# Tray2_Power.net
KiCad netlist of a schematic drawn in Altium Designer
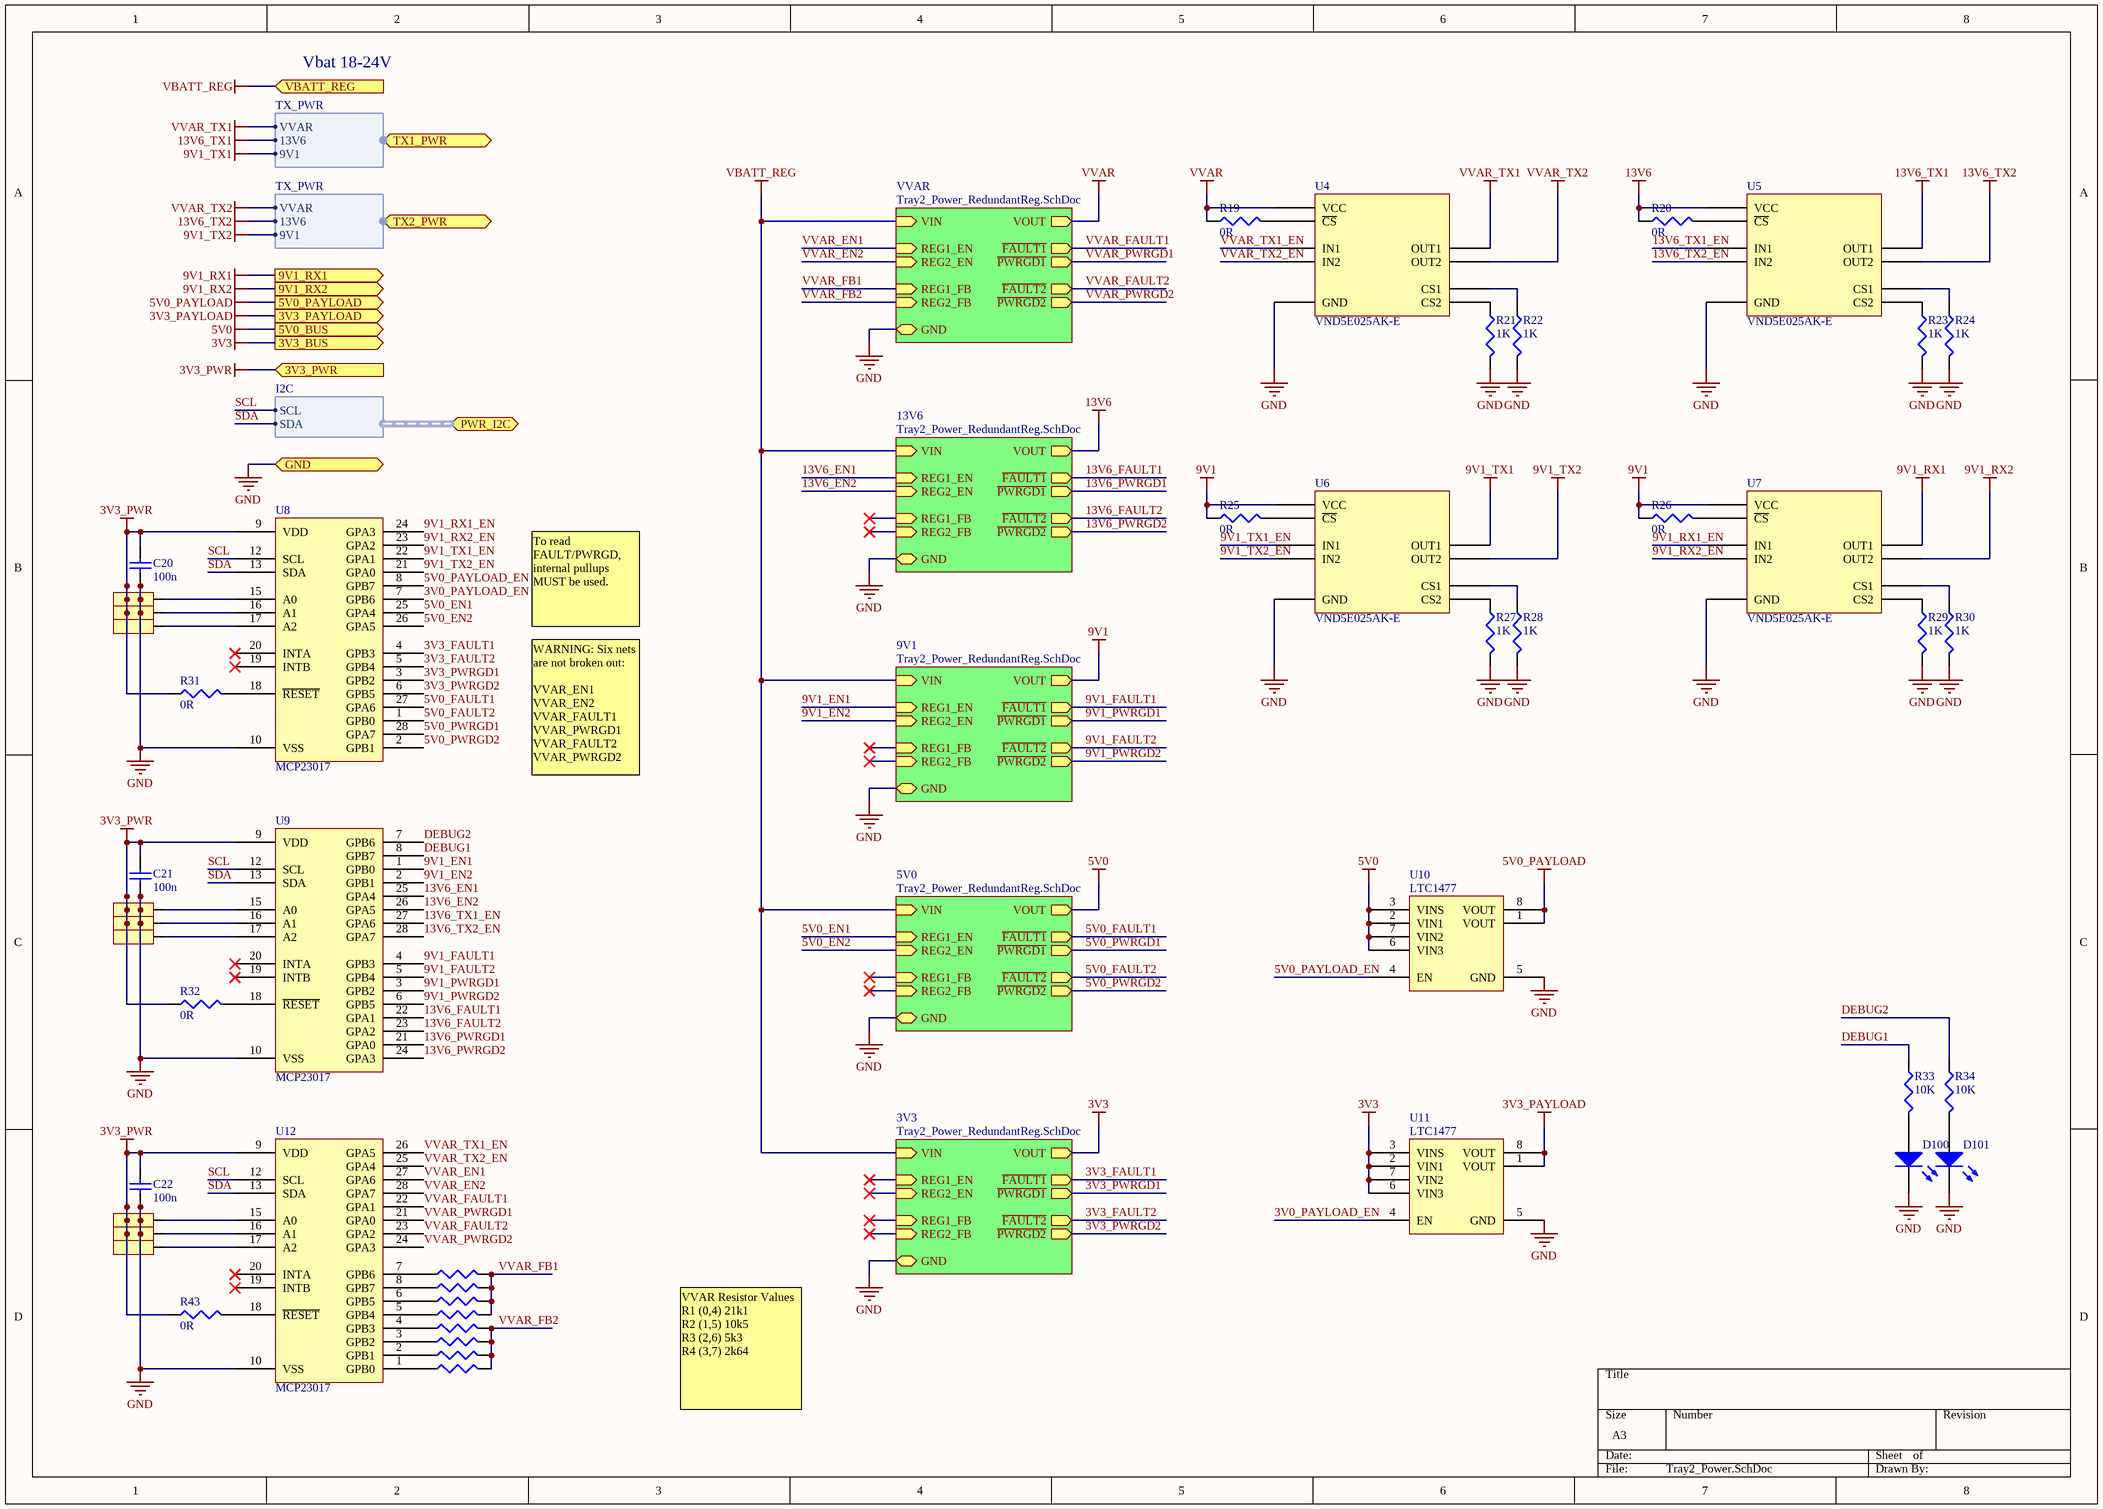
[diagram p0: Tray2_Power.SchDoc]

(export (version "E")
  (design (tool "Eeschema 10.0.6"))
  (components
    (comp (ref "C20")
      (value "100n")
      (footprint "R0805M")
      (description "Capacitor")
      (fields (field (name "PUBLISHER") "Altium Limited"))
      (libsource (lib "Miscellaneous Devices") (part "Cap"))
    )
    (comp (ref "C21")
      (value "100n")
      (footprint "R0805M")
      (description "Capacitor")
      (fields (field (name "PUBLISHER") "Altium Limited"))
      (libsource (lib "Miscellaneous Devices") (part "Cap"))
    )
    (comp (ref "C22")
      (value "100n")
      (footprint "R0805M")
      (description "Capacitor")
      (fields (field (name "PUBLISHER") "Altium Limited"))
      (libsource (lib "Miscellaneous Devices") (part "Cap"))
    )
    (comp (ref "D100")
      (value "LED0")
      (footprint "R0805M")
      (description "Typical INFRARED GaAs LED")
      (fields (field (name "PUBLISHER") "Altium Limited"))
      (libsource (lib "Miscellaneous Devices") (part "LED0"))
    )
    (comp (ref "D101")
      (value "LED0")
      (footprint "R0805M")
      (description "Typical INFRARED GaAs LED")
      (fields (field (name "PUBLISHER") "Altium Limited"))
      (libsource (lib "Miscellaneous Devices") (part "LED0"))
    )
    (comp (ref "J1")
      (value "3-WAY JUMPER")
      (footprint "J1205M")
      (libsource (lib "SchLib") (part "3-WAY JUMPER"))
    )
    (comp (ref "J2")
      (value "3-WAY JUMPER")
      (footprint "J1205M")
      (libsource (lib "SchLib") (part "3-WAY JUMPER"))
    )
    (comp (ref "J3")
      (value "3-WAY JUMPER")
      (footprint "J1205M")
      (libsource (lib "SchLib") (part "3-WAY JUMPER"))
    )
    (comp (ref "J4")
      (value "3-WAY JUMPER")
      (footprint "J1205M")
      (libsource (lib "SchLib") (part "3-WAY JUMPER"))
    )
    (comp (ref "J5")
      (value "3-WAY JUMPER")
      (footprint "J1205M")
      (libsource (lib "SchLib") (part "3-WAY JUMPER"))
    )
    (comp (ref "J6")
      (value "3-WAY JUMPER")
      (footprint "J1205M")
      (libsource (lib "SchLib") (part "3-WAY JUMPER"))
    )
    (comp (ref "J7")
      (value "3-WAY JUMPER")
      (footprint "J1205M")
      (libsource (lib "SchLib") (part "3-WAY JUMPER"))
    )
    (comp (ref "J8")
      (value "3-WAY JUMPER")
      (footprint "J1205M")
      (libsource (lib "SchLib") (part "3-WAY JUMPER"))
    )
    (comp (ref "J9")
      (value "3-WAY JUMPER")
      (footprint "J1205M")
      (libsource (lib "SchLib") (part "3-WAY JUMPER"))
    )
    (comp (ref "R19")
      (value "0R")
      (footprint "R0402M")
      (description "Resistor")
      (fields (field (name "PUBLISHER") "Altium Limited"))
      (libsource (lib "Miscellaneous Devices") (part "Res3"))
    )
    (comp (ref "R20")
      (value "0R")
      (footprint "R0402M")
      (description "Resistor")
      (fields (field (name "PUBLISHER") "Altium Limited"))
      (libsource (lib "Miscellaneous Devices") (part "Res3"))
    )
    (comp (ref "R21")
      (value "1K")
      (footprint "R0402M")
      (description "Resistor")
      (fields (field (name "PUBLISHER") "Altium Limited"))
      (libsource (lib "Miscellaneous Devices") (part "Res3"))
    )
    (comp (ref "R22")
      (value "1K")
      (footprint "R0402M")
      (description "Resistor")
      (fields (field (name "PUBLISHER") "Altium Limited"))
      (libsource (lib "Miscellaneous Devices") (part "Res3"))
    )
    (comp (ref "R23")
      (value "1K")
      (footprint "R0402M")
      (description "Resistor")
      (fields (field (name "PUBLISHER") "Altium Limited"))
      (libsource (lib "Miscellaneous Devices") (part "Res3"))
    )
    (comp (ref "R24")
      (value "1K")
      (footprint "R0402M")
      (description "Resistor")
      (fields (field (name "PUBLISHER") "Altium Limited"))
      (libsource (lib "Miscellaneous Devices") (part "Res3"))
    )
    (comp (ref "R25")
      (value "0R")
      (footprint "R0402M")
      (description "Resistor")
      (fields (field (name "PUBLISHER") "Altium Limited"))
      (libsource (lib "Miscellaneous Devices") (part "Res3"))
    )
    (comp (ref "R26")
      (value "0R")
      (footprint "R0402M")
      (description "Resistor")
      (fields (field (name "PUBLISHER") "Altium Limited"))
      (libsource (lib "Miscellaneous Devices") (part "Res3"))
    )
    (comp (ref "R27")
      (value "1K")
      (footprint "R0402M")
      (description "Resistor")
      (fields (field (name "PUBLISHER") "Altium Limited"))
      (libsource (lib "Miscellaneous Devices") (part "Res3"))
    )
    (comp (ref "R28")
      (value "1K")
      (footprint "R0402M")
      (description "Resistor")
      (fields (field (name "PUBLISHER") "Altium Limited"))
      (libsource (lib "Miscellaneous Devices") (part "Res3"))
    )
    (comp (ref "R29")
      (value "1K")
      (footprint "R0402M")
      (description "Resistor")
      (fields (field (name "PUBLISHER") "Altium Limited"))
      (libsource (lib "Miscellaneous Devices") (part "Res3"))
    )
    (comp (ref "R30")
      (value "1K")
      (footprint "R0402M")
      (description "Resistor")
      (fields (field (name "PUBLISHER") "Altium Limited"))
      (libsource (lib "Miscellaneous Devices") (part "Res3"))
    )
    (comp (ref "R31")
      (value "0R")
      (footprint "R0402M")
      (description "Resistor")
      (fields (field (name "PUBLISHER") "Altium Limited"))
      (libsource (lib "Miscellaneous Devices") (part "Res3"))
    )
    (comp (ref "R32")
      (value "0R")
      (footprint "R0402M")
      (description "Resistor")
      (fields (field (name "PUBLISHER") "Altium Limited"))
      (libsource (lib "Miscellaneous Devices") (part "Res3"))
    )
    (comp (ref "R33")
      (value "10K")
      (footprint "R0402M")
      (description "Resistor")
      (fields (field (name "PUBLISHER") "Altium Limited"))
      (libsource (lib "Miscellaneous Devices") (part "Res3"))
    )
    (comp (ref "R34")
      (value "10K")
      (footprint "R0402M")
      (description "Resistor")
      (fields (field (name "PUBLISHER") "Altium Limited"))
      (libsource (lib "Miscellaneous Devices") (part "Res3"))
    )
    (comp (ref "R35")
      (value "VSET_1")
      (footprint "R0805M")
      (description "Resistor")
      (fields (field (name "PUBLISHER") "Altium Limited"))
      (libsource (lib "Miscellaneous Devices") (part "Res3"))
    )
    (comp (ref "R36")
      (value "VSET_1")
      (footprint "R0805M")
      (description "Resistor")
      (fields (field (name "PUBLISHER") "Altium Limited"))
      (libsource (lib "Miscellaneous Devices") (part "Res3"))
    )
    (comp (ref "R37")
      (value "VSET_1")
      (footprint "R0805M")
      (description "Resistor")
      (fields (field (name "PUBLISHER") "Altium Limited"))
      (libsource (lib "Miscellaneous Devices") (part "Res3"))
    )
    (comp (ref "R38")
      (value "VSET_1")
      (footprint "R0805M")
      (description "Resistor")
      (fields (field (name "PUBLISHER") "Altium Limited"))
      (libsource (lib "Miscellaneous Devices") (part "Res3"))
    )
    (comp (ref "R39")
      (value "VSET_1")
      (footprint "R0805M")
      (description "Resistor")
      (fields (field (name "PUBLISHER") "Altium Limited"))
      (libsource (lib "Miscellaneous Devices") (part "Res3"))
    )
    (comp (ref "R40")
      (value "VSET_1")
      (footprint "R0805M")
      (description "Resistor")
      (fields (field (name "PUBLISHER") "Altium Limited"))
      (libsource (lib "Miscellaneous Devices") (part "Res3"))
    )
    (comp (ref "R41")
      (value "VSET_1")
      (footprint "R0805M")
      (description "Resistor")
      (fields (field (name "PUBLISHER") "Altium Limited"))
      (libsource (lib "Miscellaneous Devices") (part "Res3"))
    )
    (comp (ref "R42")
      (value "VSET_1")
      (footprint "R0805M")
      (description "Resistor")
      (fields (field (name "PUBLISHER") "Altium Limited"))
      (libsource (lib "Miscellaneous Devices") (part "Res3"))
    )
    (comp (ref "R43")
      (value "0R")
      (footprint "R0402M")
      (description "Resistor")
      (fields (field (name "PUBLISHER") "Altium Limited"))
      (libsource (lib "Miscellaneous Devices") (part "Res3"))
    )
    (comp (ref "U4")
      (value "VND5E025AK-E")
      (footprint "SSO24")
      (description "Double channel high-side driver with analog current sense")
      (libsource (lib "SchLib") (part "VND5E025AK-E"))
    )
    (comp (ref "U5")
      (value "VND5E025AK-E")
      (footprint "SSO24")
      (description "Double channel high-side driver with analog current sense")
      (libsource (lib "SchLib") (part "VND5E025AK-E"))
    )
    (comp (ref "U6")
      (value "VND5E025AK-E")
      (footprint "SSO24")
      (description "Double channel high-side driver with analog current sense")
      (libsource (lib "SchLib") (part "VND5E025AK-E"))
    )
    (comp (ref "U7")
      (value "VND5E025AK-E")
      (footprint "SSO24")
      (description "Double channel high-side driver with analog current sense")
      (libsource (lib "SchLib") (part "VND5E025AK-E"))
    )
    (comp (ref "U8")
      (value "MCP23017")
      (footprint "SSOP28")
      (description "16-Bit I/O Expander with Serial Interface")
      (libsource (lib "SchLib") (part "MCP23017"))
    )
    (comp (ref "U9")
      (value "MCP23017")
      (footprint "SSOP28")
      (description "16-Bit I/O Expander with Serial Interface")
      (libsource (lib "") (part "MCP23017_2"))
    )
    (comp (ref "U10")
      (value "LTC1477")
      (footprint "SO8")
      (description "Single Protected High Side Switches")
      (libsource (lib "SchLib") (part "LTC1477"))
    )
    (comp (ref "U11")
      (value "LTC1477")
      (footprint "SO8")
      (description "Single Protected High Side Switches")
      (libsource (lib "SchLib") (part "LTC1477"))
    )
    (comp (ref "U12")
      (value "MCP23017")
      (footprint "SSOP28")
      (description "16-Bit I/O Expander with Serial Interface")
      (libsource (lib "") (part "MCP23017_1"))
    )
  )
  (nets
    (net (code "3") (name "/3V0_PAYLOAD_EN") (class "Default")
      (node (ref "U11") (pin "4") (pinfunction "EN_4") (pintype "passive"))
      (node (ref "U8") (pin "7") (pinfunction "GPB6_7") (pintype "passive"))
    )
    (net (code "4") (name "/3V3_FAULT1") (class "Default")
      (node (ref "U8") (pin "4") (pinfunction "GPB3_4") (pintype "passive"))
    )
    (net (code "5") (name "/3V3_FAULT2") (class "Default")
      (node (ref "U8") (pin "5") (pinfunction "GPB4_5") (pintype "passive"))
    )
    (net (code "6") (name "/3V3_PWRGD1") (class "Default")
      (node (ref "U8") (pin "3") (pinfunction "GPB2_3") (pintype "passive"))
    )
    (net (code "7") (name "/3V3_PWRGD2") (class "Default")
      (node (ref "U8") (pin "6") (pinfunction "GPB5_6") (pintype "passive"))
    )
    (net (code "8") (name "/5V0_EN1") (class "Default")
      (node (ref "U8") (pin "25") (pinfunction "GPA4_25") (pintype "passive"))
    )
    (net (code "9") (name "/5V0_EN2") (class "Default")
      (node (ref "U8") (pin "26") (pinfunction "GPA5_26") (pintype "passive"))
    )
    (net (code "10") (name "/5V0_FAULT1") (class "Default")
      (node (ref "U8") (pin "27") (pinfunction "GPA6_27") (pintype "passive"))
    )
    (net (code "11") (name "/5V0_FAULT2") (class "Default")
      (node (ref "U8") (pin "1") (pinfunction "GPB0_1") (pintype "passive"))
    )
    (net (code "12") (name "/5V0_PAYLOAD_EN") (class "Default")
      (node (ref "U10") (pin "4") (pinfunction "EN_4") (pintype "passive"))
      (node (ref "U8") (pin "8") (pinfunction "GPB7_8") (pintype "passive"))
    )
    (net (code "13") (name "/5V0_PWRGD1") (class "Default")
      (node (ref "U8") (pin "28") (pinfunction "GPA7_28") (pintype "passive"))
    )
    (net (code "14") (name "/5V0_PWRGD2") (class "Default")
      (node (ref "U8") (pin "2") (pinfunction "GPB1_2") (pintype "passive"))
    )
    (net (code "15") (name "/9V1_EN1") (class "Default")
      (node (ref "U9") (pin "1") (pinfunction "GPB0_1") (pintype "passive"))
    )
    (net (code "16") (name "/9V1_EN2") (class "Default")
      (node (ref "U9") (pin "2") (pinfunction "GPB1_2") (pintype "passive"))
    )
    (net (code "17") (name "/9V1_FAULT1") (class "Default")
      (node (ref "U9") (pin "4") (pinfunction "GPB3_4") (pintype "passive"))
    )
    (net (code "18") (name "/9V1_FAULT2") (class "Default")
      (node (ref "U9") (pin "5") (pinfunction "GPB4_5") (pintype "passive"))
    )
    (net (code "19") (name "/9V1_PWRGD1") (class "Default")
      (node (ref "U9") (pin "3") (pinfunction "GPB2_3") (pintype "passive"))
    )
    (net (code "20") (name "/9V1_PWRGD2") (class "Default")
      (node (ref "U9") (pin "6") (pinfunction "GPB5_6") (pintype "passive"))
    )
    (net (code "21") (name "/9V1_RX1_EN") (class "Default")
      (node (ref "U7") (pin "IN1") (pinfunction "IN1_IN1") (pintype "passive"))
      (node (ref "U8") (pin "24") (pinfunction "GPA3_24") (pintype "passive"))
    )
    (net (code "22") (name "/9V1_RX2_EN") (class "Default")
      (node (ref "U7") (pin "IN2") (pinfunction "IN2_IN2") (pintype "passive"))
      (node (ref "U8") (pin "23") (pinfunction "GPA2_23") (pintype "passive"))
    )
    (net (code "23") (name "/9V1_TX1_EN") (class "Default")
      (node (ref "U6") (pin "IN1") (pinfunction "IN1_IN1") (pintype "passive"))
      (node (ref "U8") (pin "22") (pinfunction "GPA1_22") (pintype "passive"))
    )
    (net (code "24") (name "/9V1_TX2_EN") (class "Default")
      (node (ref "U6") (pin "IN2") (pinfunction "IN2_IN2") (pintype "passive"))
      (node (ref "U8") (pin "21") (pinfunction "GPA0_21") (pintype "passive"))
    )
    (net (code "25") (name "/13V6_EN1") (class "Default")
      (node (ref "U9") (pin "25") (pinfunction "GPA4_25") (pintype "passive"))
    )
    (net (code "26") (name "/13V6_EN2") (class "Default")
      (node (ref "U9") (pin "26") (pinfunction "GPA5_26") (pintype "passive"))
    )
    (net (code "27") (name "/13V6_FAULT1") (class "Default")
      (node (ref "U9") (pin "22") (pinfunction "GPA1_22") (pintype "passive"))
    )
    (net (code "28") (name "/13V6_FAULT2") (class "Default")
      (node (ref "U9") (pin "23") (pinfunction "GPA2_23") (pintype "passive"))
    )
    (net (code "29") (name "/13V6_PWRGD1") (class "Default")
      (node (ref "U9") (pin "21") (pinfunction "GPA0_21") (pintype "passive"))
    )
    (net (code "30") (name "/13V6_PWRGD2") (class "Default")
      (node (ref "U9") (pin "24") (pinfunction "GPA3_24") (pintype "passive"))
    )
    (net (code "31") (name "/13V6_TX1_EN") (class "Default")
      (node (ref "U5") (pin "IN1") (pinfunction "IN1_IN1") (pintype "passive"))
      (node (ref "U9") (pin "27") (pinfunction "GPA6_27") (pintype "passive"))
    )
    (net (code "32") (name "/13V6_TX2_EN") (class "Default")
      (node (ref "U5") (pin "IN2") (pinfunction "IN2_IN2") (pintype "passive"))
      (node (ref "U9") (pin "28") (pinfunction "GPA7_28") (pintype "passive"))
    )
    (net (code "33") (name "/DEBUG1") (class "Default")
      (node (ref "R33") (pin "1") (pinfunction "1_1") (pintype "passive"))
      (node (ref "U9") (pin "8") (pinfunction "GPB7_8") (pintype "passive"))
    )
    (net (code "34") (name "/DEBUG2") (class "Default")
      (node (ref "R34") (pin "1") (pinfunction "1_1") (pintype "passive"))
      (node (ref "U9") (pin "7") (pinfunction "GPB6_7") (pintype "passive"))
    )
    (net (code "45") (name "/SCL") (class "Default")
      (node (ref "U12") (pin "12") (pinfunction "SCL_12") (pintype "passive"))
      (node (ref "U8") (pin "12") (pinfunction "SCL_12") (pintype "passive"))
      (node (ref "U9") (pin "12") (pinfunction "SCL_12") (pintype "passive"))
    )
    (net (code "46") (name "/SDA") (class "Default")
      (node (ref "U12") (pin "13") (pinfunction "SDA_13") (pintype "passive"))
      (node (ref "U8") (pin "13") (pinfunction "SDA_13") (pintype "passive"))
      (node (ref "U9") (pin "13") (pinfunction "SDA_13") (pintype "passive"))
    )
    (net (code "47") (name "/VVAR_EN1") (class "Default")
      (node (ref "U12") (pin "27") (pinfunction "GPA6_27") (pintype "passive"))
    )
    (net (code "48") (name "/VVAR_EN2") (class "Default")
      (node (ref "U12") (pin "28") (pinfunction "GPA7_28") (pintype "passive"))
    )
    (net (code "49") (name "/VVAR_FAULT1") (class "Default")
      (node (ref "U12") (pin "22") (pinfunction "GPA1_22") (pintype "passive"))
    )
    (net (code "50") (name "/VVAR_FAULT2") (class "Default")
      (node (ref "U12") (pin "23") (pinfunction "GPA2_23") (pintype "passive"))
    )
    (net (code "51") (name "/VVAR_FB1") (class "Default")
      (node (ref "R35") (pin "2") (pinfunction "2_2") (pintype "passive"))
      (node (ref "R36") (pin "2") (pinfunction "2_2") (pintype "passive"))
      (node (ref "R37") (pin "2") (pinfunction "2_2") (pintype "passive"))
      (node (ref "R38") (pin "2") (pinfunction "2_2") (pintype "passive"))
    )
    (net (code "52") (name "/VVAR_FB2") (class "Default")
      (node (ref "R39") (pin "2") (pinfunction "2_2") (pintype "passive"))
      (node (ref "R40") (pin "2") (pinfunction "2_2") (pintype "passive"))
      (node (ref "R41") (pin "2") (pinfunction "2_2") (pintype "passive"))
      (node (ref "R42") (pin "2") (pinfunction "2_2") (pintype "passive"))
    )
    (net (code "53") (name "/VVAR_PWRGD1") (class "Default")
      (node (ref "U12") (pin "21") (pinfunction "GPA0_21") (pintype "passive"))
    )
    (net (code "54") (name "/VVAR_PWRGD2") (class "Default")
      (node (ref "U12") (pin "24") (pinfunction "GPA3_24") (pintype "passive"))
    )
    (net (code "55") (name "/VVAR_TX1_EN") (class "Default")
      (node (ref "U12") (pin "26") (pinfunction "GPA5_26") (pintype "passive"))
      (node (ref "U4") (pin "IN1") (pinfunction "IN1_IN1") (pintype "passive"))
    )
    (net (code "56") (name "/VVAR_TX2_EN") (class "Default")
      (node (ref "U12") (pin "25") (pinfunction "GPA4_25") (pintype "passive"))
      (node (ref "U4") (pin "IN2") (pinfunction "IN2_IN2") (pintype "passive"))
    )
    (net (code "59") (name "3V3") (class "Default")
      (node (ref "U11") (pin "2") (pinfunction "VIN1_2") (pintype "passive"))
      (node (ref "U11") (pin "3") (pinfunction "VINS_3") (pintype "passive"))
      (node (ref "U11") (pin "6") (pinfunction "VIN3_6") (pintype "passive"))
      (node (ref "U11") (pin "7") (pinfunction "VIN2_7") (pintype "passive"))
    )
    (net (code "60") (name "3V3_PAYLOAD") (class "Default")
      (node (ref "U11") (pin "1") (pinfunction "VOUT_1") (pintype "passive"))
      (node (ref "U11") (pin "8") (pinfunction "VOUT_8") (pintype "passive"))
    )
    (net (code "61") (name "3V3_PWR") (class "Default")
      (node (ref "C20") (pin "1") (pinfunction "1_1") (pintype "passive"))
      (node (ref "C21") (pin "1") (pinfunction "1_1") (pintype "passive"))
      (node (ref "C22") (pin "1") (pinfunction "1_1") (pintype "passive"))
      (node (ref "J1") (pin "1") (pintype "passive"))
      (node (ref "J2") (pin "1") (pintype "passive"))
      (node (ref "J3") (pin "1") (pintype "passive"))
      (node (ref "J4") (pin "1") (pintype "passive"))
      (node (ref "J5") (pin "1") (pintype "passive"))
      (node (ref "J6") (pin "1") (pintype "passive"))
      (node (ref "J7") (pin "1") (pintype "passive"))
      (node (ref "J8") (pin "1") (pintype "passive"))
      (node (ref "J9") (pin "1") (pintype "passive"))
      (node (ref "R31") (pin "1") (pinfunction "1_1") (pintype "passive"))
      (node (ref "R32") (pin "1") (pinfunction "1_1") (pintype "passive"))
      (node (ref "R43") (pin "1") (pinfunction "1_1") (pintype "passive"))
      (node (ref "U12") (pin "9") (pinfunction "VDD_9") (pintype "passive"))
      (node (ref "U8") (pin "9") (pinfunction "VDD_9") (pintype "passive"))
      (node (ref "U9") (pin "9") (pinfunction "VDD_9") (pintype "passive"))
    )
    (net (code "62") (name "5V0") (class "Default")
      (node (ref "U10") (pin "2") (pinfunction "VIN1_2") (pintype "passive"))
      (node (ref "U10") (pin "3") (pinfunction "VINS_3") (pintype "passive"))
      (node (ref "U10") (pin "6") (pinfunction "VIN3_6") (pintype "passive"))
      (node (ref "U10") (pin "7") (pinfunction "VIN2_7") (pintype "passive"))
    )
    (net (code "63") (name "5V0_PAYLOAD") (class "Default")
      (node (ref "U10") (pin "1") (pinfunction "VOUT_1") (pintype "passive"))
      (node (ref "U10") (pin "8") (pinfunction "VOUT_8") (pintype "passive"))
    )
    (net (code "64") (name "9V1") (class "Default")
      (node (ref "R25") (pin "1") (pinfunction "1_1") (pintype "passive"))
      (node (ref "R26") (pin "1") (pinfunction "1_1") (pintype "passive"))
      (node (ref "U6") (pin "VCC") (pinfunction "VCC_VCC") (pintype "passive"))
      (node (ref "U7") (pin "VCC") (pinfunction "VCC_VCC") (pintype "passive"))
    )
    (net (code "65") (name "9V1_RX1") (class "Default")
      (node (ref "U7") (pin "OUT1") (pinfunction "OUT1_OUT1") (pintype "passive"))
    )
    (net (code "66") (name "9V1_RX2") (class "Default")
      (node (ref "U7") (pin "OUT2") (pinfunction "OUT2_OUT2") (pintype "passive"))
    )
    (net (code "67") (name "9V1_TX1") (class "Default")
      (node (ref "U6") (pin "OUT1") (pinfunction "OUT1_OUT1") (pintype "passive"))
    )
    (net (code "68") (name "9V1_TX2") (class "Default")
      (node (ref "U6") (pin "OUT2") (pinfunction "OUT2_OUT2") (pintype "passive"))
    )
    (net (code "69") (name "13V6") (class "Default")
      (node (ref "R20") (pin "1") (pinfunction "1_1") (pintype "passive"))
      (node (ref "U5") (pin "VCC") (pinfunction "VCC_VCC") (pintype "passive"))
    )
    (net (code "70") (name "13V6_TX1") (class "Default")
      (node (ref "U5") (pin "OUT1") (pinfunction "OUT1_OUT1") (pintype "passive"))
    )
    (net (code "71") (name "13V6_TX2") (class "Default")
      (node (ref "U5") (pin "OUT2") (pinfunction "OUT2_OUT2") (pintype "passive"))
    )
    (net (code "72") (name "GND") (class "Default")
      (node (ref "C20") (pin "2") (pinfunction "2_2") (pintype "passive"))
      (node (ref "C21") (pin "2") (pinfunction "2_2") (pintype "passive"))
      (node (ref "C22") (pin "2") (pinfunction "2_2") (pintype "passive"))
      (node (ref "D100") (pin "2") (pinfunction "K_2") (pintype "passive"))
      (node (ref "D101") (pin "2") (pinfunction "K_2") (pintype "passive"))
      (node (ref "J1") (pin "3") (pintype "passive"))
      (node (ref "J2") (pin "3") (pintype "passive"))
      (node (ref "J3") (pin "3") (pintype "passive"))
      (node (ref "J4") (pin "3") (pintype "passive"))
      (node (ref "J5") (pin "3") (pintype "passive"))
      (node (ref "J6") (pin "3") (pintype "passive"))
      (node (ref "J7") (pin "3") (pintype "passive"))
      (node (ref "J8") (pin "3") (pintype "passive"))
      (node (ref "J9") (pin "3") (pintype "passive"))
      (node (ref "R21") (pin "2") (pinfunction "2_2") (pintype "passive"))
      (node (ref "R22") (pin "2") (pinfunction "2_2") (pintype "passive"))
      (node (ref "R23") (pin "2") (pinfunction "2_2") (pintype "passive"))
      (node (ref "R24") (pin "2") (pinfunction "2_2") (pintype "passive"))
      (node (ref "R27") (pin "2") (pinfunction "2_2") (pintype "passive"))
      (node (ref "R28") (pin "2") (pinfunction "2_2") (pintype "passive"))
      (node (ref "R29") (pin "2") (pinfunction "2_2") (pintype "passive"))
      (node (ref "R30") (pin "2") (pinfunction "2_2") (pintype "passive"))
      (node (ref "U10") (pin "5") (pinfunction "GND_5") (pintype "passive"))
      (node (ref "U11") (pin "5") (pinfunction "GND_5") (pintype "passive"))
      (node (ref "U12") (pin "10") (pinfunction "VSS_10") (pintype "passive"))
      (node (ref "U4") (pin "GND") (pinfunction "GND_GND") (pintype "passive"))
      (node (ref "U5") (pin "GND") (pinfunction "GND_GND") (pintype "passive"))
      (node (ref "U6") (pin "GND") (pinfunction "GND_GND") (pintype "passive"))
      (node (ref "U7") (pin "GND") (pinfunction "GND_GND") (pintype "passive"))
      (node (ref "U8") (pin "10") (pinfunction "VSS_10") (pintype "passive"))
      (node (ref "U9") (pin "10") (pinfunction "VSS_10") (pintype "passive"))
    )
    (net (code "73") (name "Net-(D100-A)") (class "Default")
      (node (ref "D100") (pin "1") (pinfunction "A_1") (pintype "passive"))
      (node (ref "R33") (pin "2") (pinfunction "2_2") (pintype "passive"))
    )
    (net (code "74") (name "Net-(D101-A)") (class "Default")
      (node (ref "D101") (pin "1") (pinfunction "A_1") (pintype "passive"))
      (node (ref "R34") (pin "2") (pinfunction "2_2") (pintype "passive"))
    )
    (net (code "75") (name "Net-(R21-Pad1)") (class "Default")
      (node (ref "R21") (pin "1") (pinfunction "1_1") (pintype "passive"))
      (node (ref "U4") (pin "CS2") (pinfunction "CS2_CS2") (pintype "passive"))
    )
    (net (code "76") (name "Net-(R22-Pad1)") (class "Default")
      (node (ref "R22") (pin "1") (pinfunction "1_1") (pintype "passive"))
      (node (ref "U4") (pin "CS1") (pinfunction "CS1_CS1") (pintype "passive"))
    )
    (net (code "77") (name "Net-(R23-Pad1)") (class "Default")
      (node (ref "R23") (pin "1") (pinfunction "1_1") (pintype "passive"))
      (node (ref "U5") (pin "CS2") (pinfunction "CS2_CS2") (pintype "passive"))
    )
    (net (code "78") (name "Net-(R24-Pad1)") (class "Default")
      (node (ref "R24") (pin "1") (pinfunction "1_1") (pintype "passive"))
      (node (ref "U5") (pin "CS1") (pinfunction "CS1_CS1") (pintype "passive"))
    )
    (net (code "79") (name "Net-(R27-Pad1)") (class "Default")
      (node (ref "R27") (pin "1") (pinfunction "1_1") (pintype "passive"))
      (node (ref "U6") (pin "CS2") (pinfunction "CS2_CS2") (pintype "passive"))
    )
    (net (code "80") (name "Net-(R28-Pad1)") (class "Default")
      (node (ref "R28") (pin "1") (pinfunction "1_1") (pintype "passive"))
      (node (ref "U6") (pin "CS1") (pinfunction "CS1_CS1") (pintype "passive"))
    )
    (net (code "81") (name "Net-(R29-Pad1)") (class "Default")
      (node (ref "R29") (pin "1") (pinfunction "1_1") (pintype "passive"))
      (node (ref "U7") (pin "CS2") (pinfunction "CS2_CS2") (pintype "passive"))
    )
    (net (code "82") (name "Net-(R30-Pad1)") (class "Default")
      (node (ref "R30") (pin "1") (pinfunction "1_1") (pintype "passive"))
      (node (ref "U7") (pin "CS1") (pinfunction "CS1_CS1") (pintype "passive"))
    )
    (net (code "83") (name "Net-(U4-~{CS})") (class "Default")
      (node (ref "R19") (pin "2") (pinfunction "2_2") (pintype "passive"))
      (node (ref "U4") (pin "CS_DIS") (pinfunction "~{CS}_CS_DIS") (pintype "passive"))
    )
    (net (code "84") (name "Net-(U5-~{CS})") (class "Default")
      (node (ref "R20") (pin "2") (pinfunction "2_2") (pintype "passive"))
      (node (ref "U5") (pin "CS_DIS") (pinfunction "~{CS}_CS_DIS") (pintype "passive"))
    )
    (net (code "85") (name "Net-(U6-~{CS})") (class "Default")
      (node (ref "R25") (pin "2") (pinfunction "2_2") (pintype "passive"))
      (node (ref "U6") (pin "CS_DIS") (pinfunction "~{CS}_CS_DIS") (pintype "passive"))
    )
    (net (code "86") (name "Net-(U7-~{CS})") (class "Default")
      (node (ref "R26") (pin "2") (pinfunction "2_2") (pintype "passive"))
      (node (ref "U7") (pin "CS_DIS") (pinfunction "~{CS}_CS_DIS") (pintype "passive"))
    )
    (net (code "87") (name "Net-(U8-A0)") (class "Default")
      (node (ref "J1") (pin "2") (pintype "passive"))
      (node (ref "U8") (pin "15") (pinfunction "A0_15") (pintype "passive"))
    )
    (net (code "88") (name "Net-(U8-A1)") (class "Default")
      (node (ref "J2") (pin "2") (pintype "passive"))
      (node (ref "U8") (pin "16") (pinfunction "A1_16") (pintype "passive"))
    )
    (net (code "89") (name "Net-(U8-A2)") (class "Default")
      (node (ref "J3") (pin "2") (pintype "passive"))
      (node (ref "U8") (pin "17") (pinfunction "A2_17") (pintype "passive"))
    )
    (net (code "90") (name "Net-(U8-~{RESET})") (class "Default")
      (node (ref "R31") (pin "2") (pinfunction "2_2") (pintype "passive"))
      (node (ref "U8") (pin "18") (pinfunction "~{RESET}_18") (pintype "passive"))
    )
    (net (code "91") (name "Net-(U9-A0)") (class "Default")
      (node (ref "J4") (pin "2") (pintype "passive"))
      (node (ref "U9") (pin "15") (pinfunction "A0_15") (pintype "passive"))
    )
    (net (code "92") (name "Net-(U9-A1)") (class "Default")
      (node (ref "J5") (pin "2") (pintype "passive"))
      (node (ref "U9") (pin "16") (pinfunction "A1_16") (pintype "passive"))
    )
    (net (code "93") (name "Net-(U9-A2)") (class "Default")
      (node (ref "J6") (pin "2") (pintype "passive"))
      (node (ref "U9") (pin "17") (pinfunction "A2_17") (pintype "passive"))
    )
    (net (code "94") (name "Net-(U9-~{RESET})") (class "Default")
      (node (ref "R32") (pin "2") (pinfunction "2_2") (pintype "passive"))
      (node (ref "U9") (pin "18") (pinfunction "~{RESET}_18") (pintype "passive"))
    )
    (net (code "95") (name "Net-(U12-A0)") (class "Default")
      (node (ref "J7") (pin "2") (pintype "passive"))
      (node (ref "U12") (pin "15") (pinfunction "A0_15") (pintype "passive"))
    )
    (net (code "96") (name "Net-(U12-A1)") (class "Default")
      (node (ref "J8") (pin "2") (pintype "passive"))
      (node (ref "U12") (pin "16") (pinfunction "A1_16") (pintype "passive"))
    )
    (net (code "97") (name "Net-(U12-A2)") (class "Default")
      (node (ref "J9") (pin "2") (pintype "passive"))
      (node (ref "U12") (pin "17") (pinfunction "A2_17") (pintype "passive"))
    )
    (net (code "98") (name "Net-(U12-GPB0)") (class "Default")
      (node (ref "R42") (pin "1") (pinfunction "1_1") (pintype "passive"))
      (node (ref "U12") (pin "1") (pinfunction "GPB0_1") (pintype "passive"))
    )
    (net (code "99") (name "Net-(U12-GPB1)") (class "Default")
      (node (ref "R41") (pin "1") (pinfunction "1_1") (pintype "passive"))
      (node (ref "U12") (pin "2") (pinfunction "GPB1_2") (pintype "passive"))
    )
    (net (code "100") (name "Net-(U12-GPB2)") (class "Default")
      (node (ref "R40") (pin "1") (pinfunction "1_1") (pintype "passive"))
      (node (ref "U12") (pin "3") (pinfunction "GPB2_3") (pintype "passive"))
    )
    (net (code "101") (name "Net-(U12-GPB3)") (class "Default")
      (node (ref "R39") (pin "1") (pinfunction "1_1") (pintype "passive"))
      (node (ref "U12") (pin "4") (pinfunction "GPB3_4") (pintype "passive"))
    )
    (net (code "102") (name "Net-(U12-GPB4)") (class "Default")
      (node (ref "R38") (pin "1") (pinfunction "1_1") (pintype "passive"))
      (node (ref "U12") (pin "5") (pinfunction "GPB4_5") (pintype "passive"))
    )
    (net (code "103") (name "Net-(U12-GPB5)") (class "Default")
      (node (ref "R37") (pin "1") (pinfunction "1_1") (pintype "passive"))
      (node (ref "U12") (pin "6") (pinfunction "GPB5_6") (pintype "passive"))
    )
    (net (code "104") (name "Net-(U12-GPB6)") (class "Default")
      (node (ref "R35") (pin "1") (pinfunction "1_1") (pintype "passive"))
      (node (ref "U12") (pin "7") (pinfunction "GPB6_7") (pintype "passive"))
    )
    (net (code "105") (name "Net-(U12-GPB7)") (class "Default")
      (node (ref "R36") (pin "1") (pinfunction "1_1") (pintype "passive"))
      (node (ref "U12") (pin "8") (pinfunction "GPB7_8") (pintype "passive"))
    )
    (net (code "106") (name "Net-(U12-~{RESET})") (class "Default")
      (node (ref "R43") (pin "2") (pinfunction "2_2") (pintype "passive"))
      (node (ref "U12") (pin "18") (pinfunction "~{RESET}_18") (pintype "passive"))
    )
    (net (code "108") (name "VVAR") (class "Default")
      (node (ref "R19") (pin "1") (pinfunction "1_1") (pintype "passive"))
      (node (ref "U4") (pin "VCC") (pinfunction "VCC_VCC") (pintype "passive"))
    )
    (net (code "109") (name "VVAR_TX1") (class "Default")
      (node (ref "U4") (pin "OUT1") (pinfunction "OUT1_OUT1") (pintype "passive"))
    )
    (net (code "110") (name "VVAR_TX2") (class "Default")
      (node (ref "U4") (pin "OUT2") (pinfunction "OUT2_OUT2") (pintype "passive"))
    )
    (net (code "111") (name "unconnected-(U8-INTA-Pad20)") (class "Default")
      (node (ref "U8") (pin "20") (pinfunction "INTA_20") (pintype "passive+no_connect"))
    )
    (net (code "112") (name "unconnected-(U8-INTB-Pad19)") (class "Default")
      (node (ref "U8") (pin "19") (pinfunction "INTB_19") (pintype "passive+no_connect"))
    )
    (net (code "113") (name "unconnected-(U9-INTA-Pad20)") (class "Default")
      (node (ref "U9") (pin "20") (pinfunction "INTA_20") (pintype "passive+no_connect"))
    )
    (net (code "114") (name "unconnected-(U9-INTB-Pad19)") (class "Default")
      (node (ref "U9") (pin "19") (pinfunction "INTB_19") (pintype "passive+no_connect"))
    )
    (net (code "115") (name "unconnected-(U12-INTA-Pad20)") (class "Default")
      (node (ref "U12") (pin "20") (pinfunction "INTA_20") (pintype "passive+no_connect"))
    )
    (net (code "116") (name "unconnected-(U12-INTB-Pad19)") (class "Default")
      (node (ref "U12") (pin "19") (pinfunction "INTB_19") (pintype "passive+no_connect"))
    )
  )
)
